# scarf_no_mic.net
KiCad netlist of a schematic drawn in EAGLE
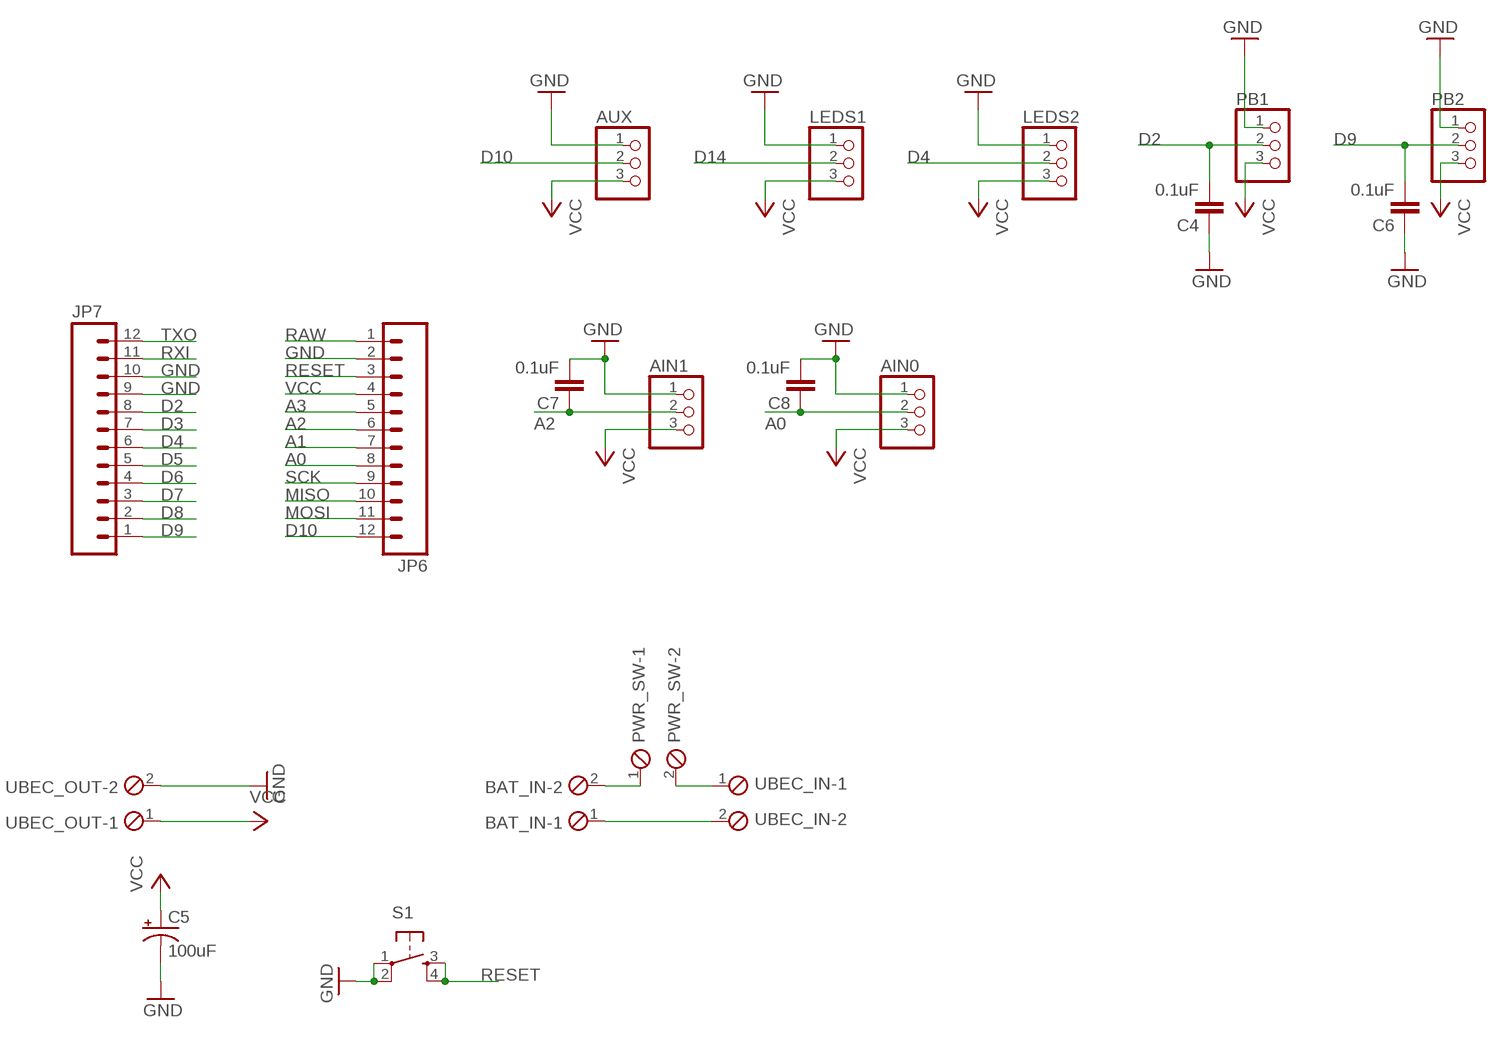
[diagram p0: schematic, sheet 1]

(export (version "E")
  (design (tool "Eeschema 10.0.6"))
  (components
    (comp (ref "AIN0")
      (value "HEADER-1X3ROUND")
      (footprint "eagle-import:1X03_ROUND")
      (libsource (lib "eagle-import") (part "HEADER-1X3ROUND"))
    )
    (comp (ref "AIN1")
      (value "HEADER-1X3ROUND")
      (footprint "eagle-import:1X03_ROUND")
      (libsource (lib "eagle-import") (part "HEADER-1X3ROUND"))
    )
    (comp (ref "AUX")
      (value "HEADER-1X3ROUND")
      (footprint "eagle-import:1X03_ROUND")
      (libsource (lib "eagle-import") (part "HEADER-1X3ROUND"))
    )
    (comp (ref "BAT_IN")
      (value "MPT2")
      (footprint "eagle-import:2POL254")
      (libsource (lib "eagle-import") (part "MPT2"))
    )
    (comp (ref "C4")
      (value "0.1uF")
      (footprint "eagle-import:C025-025X050")
      (libsource (lib "eagle-import") (part "C-EU025-025X050"))
    )
    (comp (ref "C5")
      (value "100uF")
      (footprint "eagle-import:E3,5-8")
      (libsource (lib "eagle-import") (part "CPOL-USE3.5-8"))
    )
    (comp (ref "C6")
      (value "0.1uF")
      (footprint "eagle-import:C025-025X050")
      (libsource (lib "eagle-import") (part "C-EU025-025X050"))
    )
    (comp (ref "C7")
      (value "0.1uF")
      (footprint "eagle-import:C025-025X050")
      (libsource (lib "eagle-import") (part "C-EU025-025X050"))
    )
    (comp (ref "C8")
      (value "0.1uF")
      (footprint "eagle-import:C025-025X050")
      (libsource (lib "eagle-import") (part "C-EU025-025X050"))
    )
    (comp (ref "JP6")
      (value "M12PTH")
      (footprint "eagle-import:1X12")
      (libsource (lib "eagle-import") (part "M12PTH"))
    )
    (comp (ref "JP7")
      (value "M12PTH")
      (footprint "eagle-import:1X12")
      (libsource (lib "eagle-import") (part "M12PTH"))
    )
    (comp (ref "LEDS1")
      (value "PINHD-1X3")
      (footprint "eagle-import:1X03")
      (libsource (lib "eagle-import") (part "PINHD-1X3"))
    )
    (comp (ref "LEDS2")
      (value "PINHD-1X3")
      (footprint "eagle-import:1X03")
      (libsource (lib "eagle-import") (part "PINHD-1X3"))
    )
    (comp (ref "PB1")
      (value "HEADER-1X3ROUND")
      (footprint "eagle-import:1X03_ROUND")
      (libsource (lib "eagle-import") (part "HEADER-1X3ROUND"))
    )
    (comp (ref "PB2")
      (value "HEADER-1X3ROUND")
      (footprint "eagle-import:1X03_ROUND")
      (libsource (lib "eagle-import") (part "HEADER-1X3ROUND"))
    )
    (comp (ref "PWR_SW")
      (value "MPT2")
      (footprint "eagle-import:2POL254")
      (libsource (lib "eagle-import") (part "MPT2"))
    )
    (comp (ref "S1")
      (value "TAC_SWITCHPTH")
      (footprint "eagle-import:TACTILE-PTH")
      (libsource (lib "eagle-import") (part "TAC_SWITCHPTH"))
    )
    (comp (ref "UBEC_IN")
      (value "MPT2")
      (footprint "eagle-import:2POL254")
      (libsource (lib "eagle-import") (part "MPT2"))
    )
    (comp (ref "UBEC_OUT")
      (value "MPT2")
      (footprint "eagle-import:2POL254")
      (libsource (lib "eagle-import") (part "MPT2"))
    )
  )
  (nets
    (net (code "1") (name "/A0") (class "Default")
      (node (ref "AIN0") (pin "2") (pinfunction "2_2") (pintype "passive"))
      (node (ref "C8") (pin "1") (pinfunction "1_1") (pintype "passive"))
      (node (ref "JP6") (pin "8") (pinfunction "8_8") (pintype "passive"))
    )
    (net (code "2") (name "/A1") (class "Default")
      (node (ref "JP6") (pin "7") (pinfunction "7_7") (pintype "passive"))
    )
    (net (code "3") (name "/A2") (class "Default")
      (node (ref "AIN1") (pin "2") (pinfunction "2_2") (pintype "passive"))
      (node (ref "C7") (pin "1") (pinfunction "1_1") (pintype "passive"))
      (node (ref "JP6") (pin "6") (pinfunction "6_6") (pintype "passive"))
    )
    (net (code "4") (name "/A3") (class "Default")
      (node (ref "JP6") (pin "5") (pinfunction "5_5") (pintype "passive"))
    )
    (net (code "5") (name "/D2") (class "Default")
      (node (ref "C4") (pin "2") (pinfunction "2_2") (pintype "passive"))
      (node (ref "JP7") (pin "8") (pinfunction "8_8") (pintype "passive"))
      (node (ref "PB1") (pin "2") (pinfunction "2_2") (pintype "passive"))
    )
    (net (code "6") (name "/D3") (class "Default")
      (node (ref "JP7") (pin "7") (pinfunction "7_7") (pintype "passive"))
    )
    (net (code "7") (name "/D4") (class "Default")
      (node (ref "JP7") (pin "6") (pinfunction "6_6") (pintype "passive"))
      (node (ref "LEDS2") (pin "2") (pinfunction "2_2") (pintype "passive"))
    )
    (net (code "8") (name "/D5") (class "Default")
      (node (ref "JP7") (pin "5") (pinfunction "5_5") (pintype "passive"))
    )
    (net (code "9") (name "/D6") (class "Default")
      (node (ref "JP7") (pin "4") (pinfunction "4_4") (pintype "passive"))
    )
    (net (code "10") (name "/D7") (class "Default")
      (node (ref "JP7") (pin "3") (pinfunction "3_3") (pintype "passive"))
    )
    (net (code "11") (name "/D8") (class "Default")
      (node (ref "JP7") (pin "2") (pinfunction "2_2") (pintype "passive"))
    )
    (net (code "12") (name "/D9") (class "Default")
      (node (ref "C6") (pin "2") (pinfunction "2_2") (pintype "passive"))
      (node (ref "JP7") (pin "1") (pinfunction "1_1") (pintype "passive"))
      (node (ref "PB2") (pin "2") (pinfunction "2_2") (pintype "passive"))
    )
    (net (code "13") (name "/D10") (class "Default")
      (node (ref "AUX") (pin "2") (pinfunction "2_2") (pintype "passive"))
      (node (ref "JP6") (pin "12") (pinfunction "12_12") (pintype "passive"))
    )
    (net (code "14") (name "/D14") (class "Default")
      (node (ref "LEDS1") (pin "2") (pinfunction "2_2") (pintype "passive"))
    )
    (net (code "15") (name "/MISO") (class "Default")
      (node (ref "JP6") (pin "10") (pinfunction "10_10") (pintype "passive"))
    )
    (net (code "16") (name "/MOSI") (class "Default")
      (node (ref "JP6") (pin "11") (pinfunction "11_11") (pintype "passive"))
    )
    (net (code "17") (name "/RAW") (class "Default")
      (node (ref "JP6") (pin "1") (pinfunction "1_1") (pintype "passive"))
    )
    (net (code "18") (name "/RESET") (class "Default")
      (node (ref "JP6") (pin "3") (pinfunction "3_3") (pintype "passive"))
      (node (ref "S1") (pin "3") (pinfunction "3_3") (pintype "passive"))
      (node (ref "S1") (pin "4") (pinfunction "4_4") (pintype "passive"))
    )
    (net (code "19") (name "/RXI") (class "Default")
      (node (ref "JP7") (pin "11") (pinfunction "11_11") (pintype "passive"))
    )
    (net (code "20") (name "/SCK") (class "Default")
      (node (ref "JP6") (pin "9") (pinfunction "9_9") (pintype "passive"))
    )
    (net (code "21") (name "/TXO") (class "Default")
      (node (ref "JP7") (pin "12") (pinfunction "12_12") (pintype "passive"))
    )
    (net (code "22") (name "GND") (class "Default")
      (node (ref "AIN0") (pin "1") (pinfunction "1_1") (pintype "passive"))
      (node (ref "AIN1") (pin "1") (pinfunction "1_1") (pintype "passive"))
      (node (ref "AUX") (pin "1") (pinfunction "1_1") (pintype "passive"))
      (node (ref "C4") (pin "1") (pinfunction "1_1") (pintype "passive"))
      (node (ref "C5") (pin "-") (pinfunction "-_-") (pintype "passive"))
      (node (ref "C6") (pin "1") (pinfunction "1_1") (pintype "passive"))
      (node (ref "C7") (pin "2") (pinfunction "2_2") (pintype "passive"))
      (node (ref "C8") (pin "2") (pinfunction "2_2") (pintype "passive"))
      (node (ref "JP6") (pin "2") (pinfunction "2_2") (pintype "passive"))
      (node (ref "JP7") (pin "10") (pinfunction "10_10") (pintype "passive"))
      (node (ref "JP7") (pin "9") (pinfunction "9_9") (pintype "passive"))
      (node (ref "LEDS1") (pin "1") (pinfunction "1_1") (pintype "passive"))
      (node (ref "LEDS2") (pin "1") (pinfunction "1_1") (pintype "passive"))
      (node (ref "PB1") (pin "1") (pinfunction "1_1") (pintype "passive"))
      (node (ref "PB2") (pin "1") (pinfunction "1_1") (pintype "passive"))
      (node (ref "S1") (pin "1") (pinfunction "1_1") (pintype "passive"))
      (node (ref "S1") (pin "2") (pinfunction "2_2") (pintype "passive"))
      (node (ref "UBEC_OUT") (pin "2") (pinfunction "1_2") (pintype "passive"))
    )
    (net (code "23") (name "Net-(BAT_INB-1)") (class "Default")
      (node (ref "BAT_IN") (pin "2") (pinfunction "1_2") (pintype "passive"))
      (node (ref "PWR_SW") (pin "1") (pinfunction "1_1") (pintype "passive"))
    )
    (net (code "24") (name "Net-(PWR_SWB-1)") (class "Default")
      (node (ref "PWR_SW") (pin "2") (pinfunction "1_2") (pintype "passive"))
      (node (ref "UBEC_IN") (pin "1") (pinfunction "1_1") (pintype "passive"))
    )
    (net (code "25") (name "Net-(UBEC_INB-1)") (class "Default")
      (node (ref "BAT_IN") (pin "1") (pinfunction "1_1") (pintype "passive"))
      (node (ref "UBEC_IN") (pin "2") (pinfunction "1_2") (pintype "passive"))
    )
    (net (code "26") (name "VCC") (class "Default")
      (node (ref "AIN0") (pin "3") (pinfunction "3_3") (pintype "passive"))
      (node (ref "AIN1") (pin "3") (pinfunction "3_3") (pintype "passive"))
      (node (ref "AUX") (pin "3") (pinfunction "3_3") (pintype "passive"))
      (node (ref "C5") (pin "+") (pinfunction "+_+") (pintype "passive"))
      (node (ref "JP6") (pin "4") (pinfunction "4_4") (pintype "passive"))
      (node (ref "LEDS1") (pin "3") (pinfunction "3_3") (pintype "passive"))
      (node (ref "LEDS2") (pin "3") (pinfunction "3_3") (pintype "passive"))
      (node (ref "PB1") (pin "3") (pinfunction "3_3") (pintype "passive"))
      (node (ref "PB2") (pin "3") (pinfunction "3_3") (pintype "passive"))
      (node (ref "UBEC_OUT") (pin "1") (pinfunction "1_1") (pintype "passive"))
    )
  )
)
